# serial.net
KiCad netlist of a schematic drawn in EAGLE
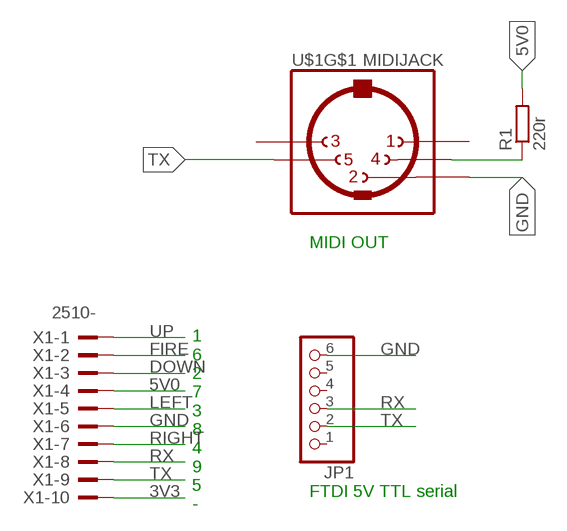
[diagram p0: schematic, sheet 1]

(export (version "E")
  (design (tool "Eeschema 10.0.6"))
  (components
    (comp (ref "JP1")
      (value "PINHD-1X6CB")
      (footprint "eagle-import:1X06-CLEANBIG")
      (libsource (lib "eagle-import") (part "PINHD-1X6CB"))
    )
    (comp (ref "R1")
      (value "220r")
      (footprint "eagle-import:0204_7")
      (libsource (lib "eagle-import") (part "R-EU_0204/7"))
    )
    (comp (ref "U$1")
      (value "MIDIJACK")
      (footprint "eagle-import:CP-2350")
      (libsource (lib "eagle-import") (part "MIDIJACK"))
    )
    (comp (ref "X1")
      (value "2510-")
      (footprint "eagle-import:PAK100_2500-10")
      (fields (field (name "MF") "3M") (field (name "MPN") "2510-6002UB"))
      (libsource (lib "eagle-import") (part "2510-"))
    )
  )
  (nets
    (net (code "1") (name "/3V3") (class "Default")
      (node (ref "X1") (pin "10") (pinfunction "KL_10") (pintype "passive"))
    )
    (net (code "2") (name "/DOWN") (class "Default")
      (node (ref "X1") (pin "3") (pinfunction "KL_3") (pintype "passive"))
    )
    (net (code "3") (name "/FIRE") (class "Default")
      (node (ref "X1") (pin "2") (pinfunction "KL_2") (pintype "passive"))
    )
    (net (code "4") (name "/LEFT") (class "Default")
      (node (ref "X1") (pin "5") (pinfunction "KL_5") (pintype "passive"))
    )
    (net (code "5") (name "/RIGHT") (class "Default")
      (node (ref "X1") (pin "7") (pinfunction "KL_7") (pintype "passive"))
    )
    (net (code "6") (name "/RX") (class "Default")
      (node (ref "JP1") (pin "3") (pinfunction "3_3") (pintype "passive"))
      (node (ref "X1") (pin "8") (pinfunction "KL_8") (pintype "passive"))
    )
    (net (code "7") (name "/UP") (class "Default")
      (node (ref "X1") (pin "1") (pinfunction "KL_1") (pintype "passive"))
    )
    (net (code "8") (name "5V0") (class "Default")
      (node (ref "R1") (pin "2") (pinfunction "2_2") (pintype "passive"))
      (node (ref "X1") (pin "4") (pinfunction "KL_4") (pintype "passive"))
    )
    (net (code "9") (name "GND") (class "Default")
      (node (ref "JP1") (pin "6") (pinfunction "6_6") (pintype "passive"))
      (node (ref "U$1") (pin "2") (pinfunction "2_2") (pintype "passive"))
      (node (ref "X1") (pin "6") (pinfunction "KL_6") (pintype "passive"))
    )
    (net (code "10") (name "Net-(R1-Pad1)") (class "Default")
      (node (ref "R1") (pin "1") (pinfunction "1_1") (pintype "passive"))
      (node (ref "U$1") (pin "4") (pinfunction "4_4") (pintype "passive"))
    )
    (net (code "11") (name "TX") (class "Default")
      (node (ref "JP1") (pin "2") (pinfunction "2_2") (pintype "passive"))
      (node (ref "U$1") (pin "5") (pinfunction "5_5") (pintype "passive"))
      (node (ref "X1") (pin "9") (pinfunction "KL_9") (pintype "passive"))
    )
    (net (code "12") (name "unconnected-(JP1-Pad1)") (class "Default")
      (node (ref "JP1") (pin "1") (pinfunction "1_1") (pintype "passive"))
    )
    (net (code "13") (name "unconnected-(JP1-Pad4)") (class "Default")
      (node (ref "JP1") (pin "4") (pinfunction "4_4") (pintype "passive"))
    )
    (net (code "14") (name "unconnected-(JP1-Pad5)") (class "Default")
      (node (ref "JP1") (pin "5") (pinfunction "5_5") (pintype "passive"))
    )
    (net (code "15") (name "unconnected-(U$1-Pad1)") (class "Default")
      (node (ref "U$1") (pin "1") (pinfunction "1_1") (pintype "passive"))
    )
    (net (code "16") (name "unconnected-(U$1-Pad3)") (class "Default")
      (node (ref "U$1") (pin "3") (pinfunction "3_3") (pintype "passive"))
    )
  )
)
